# LED_16x_Schematic.net
KiCad netlist of a schematic drawn in Altium Designer
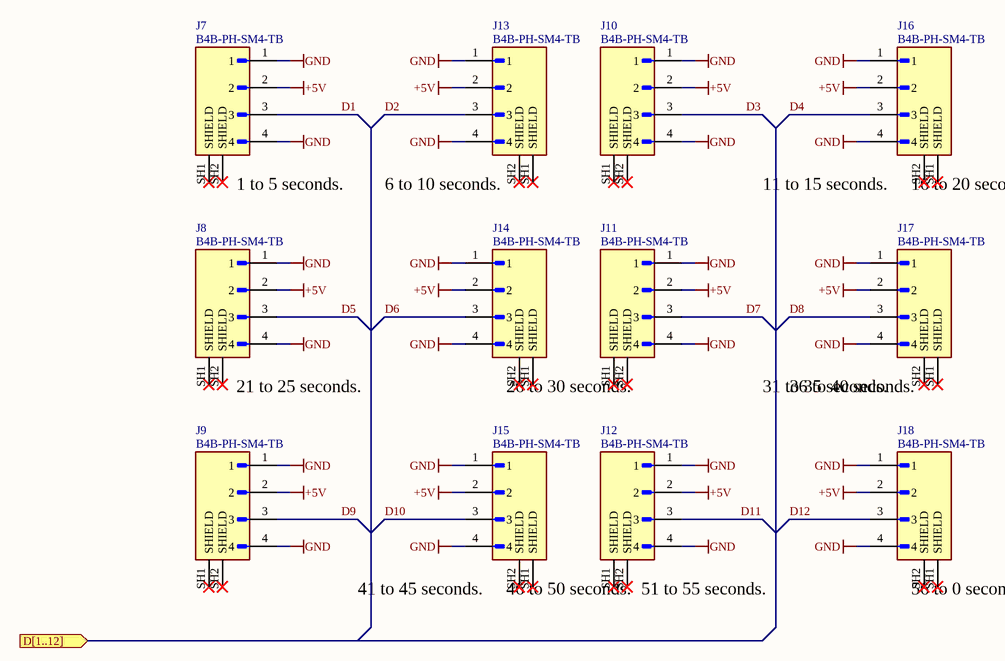
[diagram p0: LED_16x_Schematic.SchDoc]

(export (version "E")
  (design (tool "Eeschema 10.0.6"))
  (components
    (comp (ref "J7")
      (value "B4B-PH-SM4-TB")
      (footprint "PCB_Altium_Library_Manuel:Connector_SMD")
      (description "CONN HEADER SMD 4POS 2MM.")
      (libsource (lib "") (part "Connector_SMD_1"))
    )
    (comp (ref "J8")
      (value "B4B-PH-SM4-TB")
      (footprint "PCB_Altium_Library_Manuel:Connector_SMD")
      (description "CONN HEADER SMD 4POS 2MM.")
      (libsource (lib "") (part "Connector_SMD_1"))
    )
    (comp (ref "J9")
      (value "B4B-PH-SM4-TB")
      (footprint "PCB_Altium_Library_Manuel:Connector_SMD")
      (description "CONN HEADER SMD 4POS 2MM.")
      (libsource (lib "") (part "Connector_SMD_1"))
    )
    (comp (ref "J10")
      (value "B4B-PH-SM4-TB")
      (footprint "PCB_Altium_Library_Manuel:Connector_SMD")
      (description "CONN HEADER SMD 4POS 2MM.")
      (libsource (lib "") (part "Connector_SMD_1"))
    )
    (comp (ref "J11")
      (value "B4B-PH-SM4-TB")
      (footprint "PCB_Altium_Library_Manuel:Connector_SMD")
      (description "CONN HEADER SMD 4POS 2MM.")
      (libsource (lib "") (part "Connector_SMD_1"))
    )
    (comp (ref "J12")
      (value "B4B-PH-SM4-TB")
      (footprint "PCB_Altium_Library_Manuel:Connector_SMD")
      (description "CONN HEADER SMD 4POS 2MM.")
      (libsource (lib "") (part "Connector_SMD_1"))
    )
    (comp (ref "J13")
      (value "B4B-PH-SM4-TB")
      (footprint "PCB_Altium_Library_Manuel:Connector_SMD")
      (description "CONN HEADER SMD 4POS 2MM.")
      (libsource (lib "Schematic_Altium_Library_Manuel") (part "Connector_SMD"))
    )
    (comp (ref "J14")
      (value "B4B-PH-SM4-TB")
      (footprint "PCB_Altium_Library_Manuel:Connector_SMD")
      (description "CONN HEADER SMD 4POS 2MM.")
      (libsource (lib "Schematic_Altium_Library_Manuel") (part "Connector_SMD"))
    )
    (comp (ref "J15")
      (value "B4B-PH-SM4-TB")
      (footprint "PCB_Altium_Library_Manuel:Connector_SMD")
      (description "CONN HEADER SMD 4POS 2MM.")
      (libsource (lib "Schematic_Altium_Library_Manuel") (part "Connector_SMD"))
    )
    (comp (ref "J16")
      (value "B4B-PH-SM4-TB")
      (footprint "PCB_Altium_Library_Manuel:Connector_SMD")
      (description "CONN HEADER SMD 4POS 2MM.")
      (libsource (lib "Schematic_Altium_Library_Manuel") (part "Connector_SMD"))
    )
    (comp (ref "J17")
      (value "B4B-PH-SM4-TB")
      (footprint "PCB_Altium_Library_Manuel:Connector_SMD")
      (description "CONN HEADER SMD 4POS 2MM.")
      (libsource (lib "Schematic_Altium_Library_Manuel") (part "Connector_SMD"))
    )
    (comp (ref "J18")
      (value "B4B-PH-SM4-TB")
      (footprint "PCB_Altium_Library_Manuel:Connector_SMD")
      (description "CONN HEADER SMD 4POS 2MM.")
      (libsource (lib "Schematic_Altium_Library_Manuel") (part "Connector_SMD"))
    )
  )
  (nets
    (net (code "1") (name "+5V") (class "Default")
      (node (ref "J10") (pin "2") (pinfunction "2_2") (pintype "passive"))
      (node (ref "J11") (pin "2") (pinfunction "2_2") (pintype "passive"))
      (node (ref "J12") (pin "2") (pinfunction "2_2") (pintype "passive"))
      (node (ref "J13") (pin "2") (pinfunction "2_2") (pintype "passive"))
      (node (ref "J14") (pin "2") (pinfunction "2_2") (pintype "passive"))
      (node (ref "J15") (pin "2") (pinfunction "2_2") (pintype "passive"))
      (node (ref "J16") (pin "2") (pinfunction "2_2") (pintype "passive"))
      (node (ref "J17") (pin "2") (pinfunction "2_2") (pintype "passive"))
      (node (ref "J18") (pin "2") (pinfunction "2_2") (pintype "passive"))
      (node (ref "J7") (pin "2") (pinfunction "2_2") (pintype "passive"))
      (node (ref "J8") (pin "2") (pinfunction "2_2") (pintype "passive"))
      (node (ref "J9") (pin "2") (pinfunction "2_2") (pintype "passive"))
    )
    (net (code "2") (name "/D1") (class "Default")
      (node (ref "J7") (pin "3") (pinfunction "3_3") (pintype "passive"))
    )
    (net (code "3") (name "/D2") (class "Default")
      (node (ref "J13") (pin "3") (pinfunction "3_3") (pintype "passive"))
    )
    (net (code "4") (name "/D3") (class "Default")
      (node (ref "J10") (pin "3") (pinfunction "3_3") (pintype "passive"))
    )
    (net (code "5") (name "/D4") (class "Default")
      (node (ref "J16") (pin "3") (pinfunction "3_3") (pintype "passive"))
    )
    (net (code "6") (name "/D5") (class "Default")
      (node (ref "J8") (pin "3") (pinfunction "3_3") (pintype "passive"))
    )
    (net (code "7") (name "/D6") (class "Default")
      (node (ref "J14") (pin "3") (pinfunction "3_3") (pintype "passive"))
    )
    (net (code "8") (name "/D7") (class "Default")
      (node (ref "J11") (pin "3") (pinfunction "3_3") (pintype "passive"))
    )
    (net (code "9") (name "/D8") (class "Default")
      (node (ref "J17") (pin "3") (pinfunction "3_3") (pintype "passive"))
    )
    (net (code "10") (name "/D9") (class "Default")
      (node (ref "J9") (pin "3") (pinfunction "3_3") (pintype "passive"))
    )
    (net (code "11") (name "/D10") (class "Default")
      (node (ref "J15") (pin "3") (pinfunction "3_3") (pintype "passive"))
    )
    (net (code "12") (name "/D11") (class "Default")
      (node (ref "J12") (pin "3") (pinfunction "3_3") (pintype "passive"))
    )
    (net (code "13") (name "/D12") (class "Default")
      (node (ref "J18") (pin "3") (pinfunction "3_3") (pintype "passive"))
    )
    (net (code "15") (name "GND") (class "Default")
      (node (ref "J10") (pin "1") (pinfunction "1_1") (pintype "passive"))
      (node (ref "J10") (pin "4") (pinfunction "4_4") (pintype "passive"))
      (node (ref "J11") (pin "1") (pinfunction "1_1") (pintype "passive"))
      (node (ref "J11") (pin "4") (pinfunction "4_4") (pintype "passive"))
      (node (ref "J12") (pin "1") (pinfunction "1_1") (pintype "passive"))
      (node (ref "J12") (pin "4") (pinfunction "4_4") (pintype "passive"))
      (node (ref "J13") (pin "1") (pinfunction "1_1") (pintype "passive"))
      (node (ref "J13") (pin "4") (pinfunction "4_4") (pintype "passive"))
      (node (ref "J14") (pin "1") (pinfunction "1_1") (pintype "passive"))
      (node (ref "J14") (pin "4") (pinfunction "4_4") (pintype "passive"))
      (node (ref "J15") (pin "1") (pinfunction "1_1") (pintype "passive"))
      (node (ref "J15") (pin "4") (pinfunction "4_4") (pintype "passive"))
      (node (ref "J16") (pin "1") (pinfunction "1_1") (pintype "passive"))
      (node (ref "J16") (pin "4") (pinfunction "4_4") (pintype "passive"))
      (node (ref "J17") (pin "1") (pinfunction "1_1") (pintype "passive"))
      (node (ref "J17") (pin "4") (pinfunction "4_4") (pintype "passive"))
      (node (ref "J18") (pin "1") (pinfunction "1_1") (pintype "passive"))
      (node (ref "J18") (pin "4") (pinfunction "4_4") (pintype "passive"))
      (node (ref "J7") (pin "1") (pinfunction "1_1") (pintype "passive"))
      (node (ref "J7") (pin "4") (pinfunction "4_4") (pintype "passive"))
      (node (ref "J8") (pin "1") (pinfunction "1_1") (pintype "passive"))
      (node (ref "J8") (pin "4") (pinfunction "4_4") (pintype "passive"))
      (node (ref "J9") (pin "1") (pinfunction "1_1") (pintype "passive"))
      (node (ref "J9") (pin "4") (pinfunction "4_4") (pintype "passive"))
    )
    (net (code "16") (name "unconnected-(J7-SHIELD-PadSH1)") (class "Default")
      (node (ref "J7") (pin "SH1") (pinfunction "SHIELD_SH1") (pintype "passive+no_connect"))
    )
    (net (code "17") (name "unconnected-(J7-SHIELD-PadSH2)") (class "Default")
      (node (ref "J7") (pin "SH2") (pinfunction "SHIELD_SH2") (pintype "passive+no_connect"))
    )
    (net (code "18") (name "unconnected-(J8-SHIELD-PadSH1)") (class "Default")
      (node (ref "J8") (pin "SH1") (pinfunction "SHIELD_SH1") (pintype "passive+no_connect"))
    )
    (net (code "19") (name "unconnected-(J8-SHIELD-PadSH2)") (class "Default")
      (node (ref "J8") (pin "SH2") (pinfunction "SHIELD_SH2") (pintype "passive+no_connect"))
    )
    (net (code "20") (name "unconnected-(J9-SHIELD-PadSH1)") (class "Default")
      (node (ref "J9") (pin "SH1") (pinfunction "SHIELD_SH1") (pintype "passive+no_connect"))
    )
    (net (code "21") (name "unconnected-(J9-SHIELD-PadSH2)") (class "Default")
      (node (ref "J9") (pin "SH2") (pinfunction "SHIELD_SH2") (pintype "passive+no_connect"))
    )
    (net (code "22") (name "unconnected-(J10-SHIELD-PadSH1)") (class "Default")
      (node (ref "J10") (pin "SH1") (pinfunction "SHIELD_SH1") (pintype "passive+no_connect"))
    )
    (net (code "23") (name "unconnected-(J10-SHIELD-PadSH2)") (class "Default")
      (node (ref "J10") (pin "SH2") (pinfunction "SHIELD_SH2") (pintype "passive+no_connect"))
    )
    (net (code "24") (name "unconnected-(J11-SHIELD-PadSH1)") (class "Default")
      (node (ref "J11") (pin "SH1") (pinfunction "SHIELD_SH1") (pintype "passive+no_connect"))
    )
    (net (code "25") (name "unconnected-(J11-SHIELD-PadSH2)") (class "Default")
      (node (ref "J11") (pin "SH2") (pinfunction "SHIELD_SH2") (pintype "passive+no_connect"))
    )
    (net (code "26") (name "unconnected-(J12-SHIELD-PadSH1)") (class "Default")
      (node (ref "J12") (pin "SH1") (pinfunction "SHIELD_SH1") (pintype "passive+no_connect"))
    )
    (net (code "27") (name "unconnected-(J12-SHIELD-PadSH2)") (class "Default")
      (node (ref "J12") (pin "SH2") (pinfunction "SHIELD_SH2") (pintype "passive+no_connect"))
    )
    (net (code "28") (name "unconnected-(J13-SHIELD-PadSH1)") (class "Default")
      (node (ref "J13") (pin "SH1") (pinfunction "SHIELD_SH1") (pintype "passive+no_connect"))
    )
    (net (code "29") (name "unconnected-(J13-SHIELD-PadSH2)") (class "Default")
      (node (ref "J13") (pin "SH2") (pinfunction "SHIELD_SH2") (pintype "passive+no_connect"))
    )
    (net (code "30") (name "unconnected-(J14-SHIELD-PadSH1)") (class "Default")
      (node (ref "J14") (pin "SH1") (pinfunction "SHIELD_SH1") (pintype "passive+no_connect"))
    )
    (net (code "31") (name "unconnected-(J14-SHIELD-PadSH2)") (class "Default")
      (node (ref "J14") (pin "SH2") (pinfunction "SHIELD_SH2") (pintype "passive+no_connect"))
    )
    (net (code "32") (name "unconnected-(J15-SHIELD-PadSH1)") (class "Default")
      (node (ref "J15") (pin "SH1") (pinfunction "SHIELD_SH1") (pintype "passive+no_connect"))
    )
    (net (code "33") (name "unconnected-(J15-SHIELD-PadSH2)") (class "Default")
      (node (ref "J15") (pin "SH2") (pinfunction "SHIELD_SH2") (pintype "passive+no_connect"))
    )
    (net (code "34") (name "unconnected-(J16-SHIELD-PadSH1)") (class "Default")
      (node (ref "J16") (pin "SH1") (pinfunction "SHIELD_SH1") (pintype "passive+no_connect"))
    )
    (net (code "35") (name "unconnected-(J16-SHIELD-PadSH2)") (class "Default")
      (node (ref "J16") (pin "SH2") (pinfunction "SHIELD_SH2") (pintype "passive+no_connect"))
    )
    (net (code "36") (name "unconnected-(J17-SHIELD-PadSH1)") (class "Default")
      (node (ref "J17") (pin "SH1") (pinfunction "SHIELD_SH1") (pintype "passive+no_connect"))
    )
    (net (code "37") (name "unconnected-(J17-SHIELD-PadSH2)") (class "Default")
      (node (ref "J17") (pin "SH2") (pinfunction "SHIELD_SH2") (pintype "passive+no_connect"))
    )
    (net (code "38") (name "unconnected-(J18-SHIELD-PadSH1)") (class "Default")
      (node (ref "J18") (pin "SH1") (pinfunction "SHIELD_SH1") (pintype "passive+no_connect"))
    )
    (net (code "39") (name "unconnected-(J18-SHIELD-PadSH2)") (class "Default")
      (node (ref "J18") (pin "SH2") (pinfunction "SHIELD_SH2") (pintype "passive+no_connect"))
    )
  )
)
